# design.net
KiCad netlist of a schematic drawn in Altium Designer
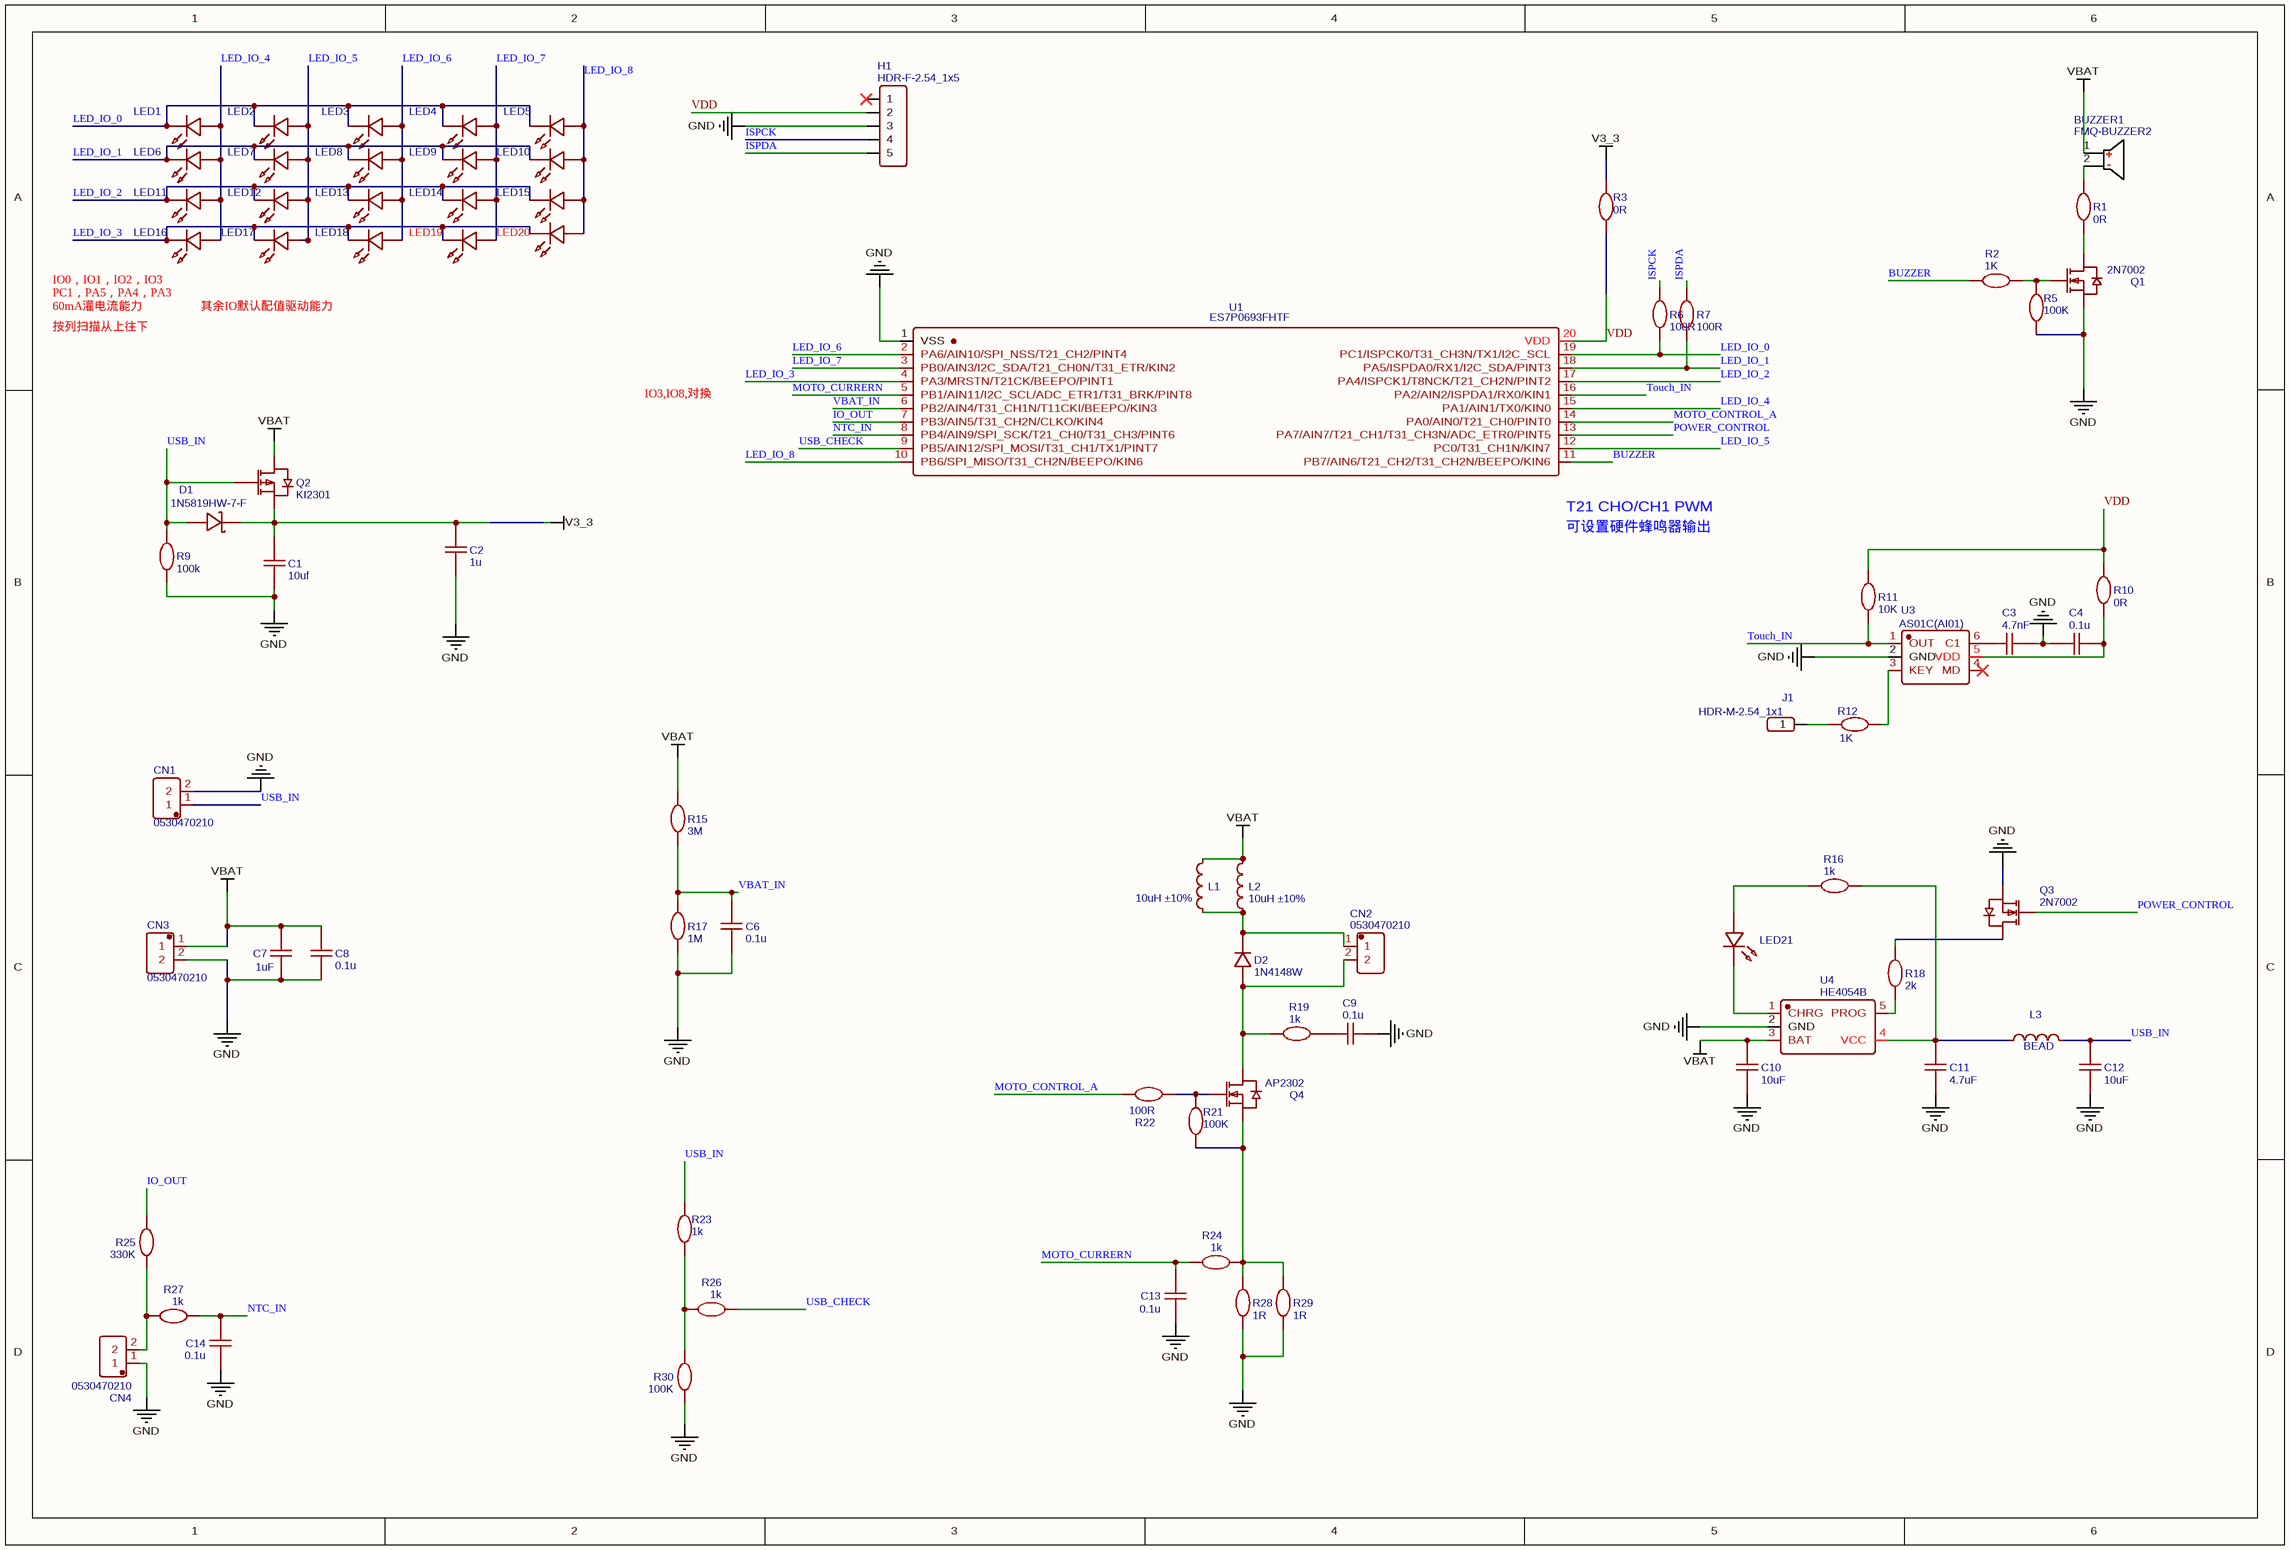
[diagram p0: 搅拌杯原理图.schdoc]

(export (version "E")
  (design (tool "Eeschema 10.0.6"))
  (components
    (comp (ref "BUZZER1")
      (value "FMQ-BUZZER2")
      (footprint "BUZ-TH_BD12.0-P7.60-D0.6-FD")
      (fields (field (name "BOM_SUPPLIER PART") "C9900006103") (field (name "CONTRIBUTOR") "LCSC"))
      (libsource (lib "altium-import") (part "root_0_FMQ-BUZZER2_"))
    )
    (comp (ref "C1")
      (value "10uf")
      (footprint "C0603")
      (fields
        (field (name "BOM_SUPPLIER PART") "C87148")
        (field (name "BOM_MANUFACTURER PART") "JMK105CBJ106MV-F")
        (field (name "CONTRIBUTOR") "LCEDA_Lib")
      )
      (libsource (lib "altium-import") (part "root_1_10uf_"))
    )
    (comp (ref "C2")
      (value "1u")
      (footprint "C0603")
      (fields (field (name "CONTRIBUTOR") "LCEDA_Lib"))
      (libsource (lib "altium-import") (part "root_1_1u_"))
    )
    (comp (ref "C3")
      (value "4.7nF")
      (footprint "C0603")
      (fields (field (name "CONTRIBUTOR") "LCEDA_Lib"))
      (libsource (lib "altium-import") (part "root_0_4.7nF_"))
    )
    (comp (ref "C4")
      (value "0.1u")
      (footprint "C0603")
      (fields (field (name "CONTRIBUTOR") "LCEDA_Lib"))
      (libsource (lib "altium-import") (part "root_0_0.1u_"))
    )
    (comp (ref "C6")
      (value "0.1u")
      (footprint "C0603")
      (fields (field (name "CONTRIBUTOR") "LCEDA_Lib"))
      (libsource (lib "") (part "root_1_0.1u__1"))
    )
    (comp (ref "C7")
      (value "1uF")
      (footprint "C0603")
      (fields (field (name "CONTRIBUTOR") "LCEDA_Lib"))
      (libsource (lib "altium-import") (part "root_3_1uF_"))
    )
    (comp (ref "C8")
      (value "0.1u")
      (footprint "C0603")
      (fields (field (name "CONTRIBUTOR") "LCEDA_Lib"))
      (libsource (lib "") (part "root_3_0.1u__1"))
    )
    (comp (ref "C9")
      (value "0.1u")
      (footprint "C0603")
      (fields (field (name "CONTRIBUTOR") "LCEDA_Lib"))
      (libsource (lib "altium-import") (part "root_2_0.1u_"))
    )
    (comp (ref "C10")
      (value "10uF")
      (footprint "C0603")
      (fields (field (name "CONTRIBUTOR") "LCEDA_Lib"))
      (libsource (lib "altium-import") (part "root_1_10uF_"))
    )
    (comp (ref "C11")
      (value "4.7uF")
      (footprint "C0603")
      (fields (field (name "CONTRIBUTOR") "LCEDA_Lib"))
      (libsource (lib "altium-import") (part "root_1_4.7uF_"))
    )
    (comp (ref "C12")
      (value "10uF")
      (footprint "C0603")
      (fields (field (name "CONTRIBUTOR") "LCEDA_Lib"))
      (libsource (lib "altium-import") (part "root_1_10uF_"))
    )
    (comp (ref "C13")
      (value "0.1u")
      (footprint "C0603")
      (fields (field (name "CONTRIBUTOR") "LCEDA_Lib"))
      (libsource (lib "altium-import") (part "root_1_0.1u_"))
    )
    (comp (ref "C14")
      (value "0.1u")
      (footprint "C0603")
      (fields (field (name "CONTRIBUTOR") "LCEDA_Lib"))
      (libsource (lib "altium-import") (part "root_3_0.1u_"))
    )
    (comp (ref "CN1")
      (value "0530470210")
      (footprint "CONN-TH_0530470210")
      (fields (field (name "BOM_SUPPLIER PART") "C114130") (field (name "CONTRIBUTOR") "LCSC"))
      (libsource (lib "altium-import") (part "root_0_mirrored_0530470210_"))
    )
    (comp (ref "CN2")
      (value "0530470210")
      (footprint "CONN-TH_0530470210")
      (fields (field (name "BOM_SUPPLIER PART") "C114130") (field (name "CONTRIBUTOR") "LCSC"))
      (libsource (lib "altium-import") (part "root_0_0530470210_"))
    )
    (comp (ref "CN3")
      (value "0530470210")
      (footprint "CONN-TH_0530470210")
      (fields (field (name "BOM_SUPPLIER PART") "C114130") (field (name "CONTRIBUTOR") "LCSC"))
      (libsource (lib "") (part "root_0_mirrored_0530470210__1"))
    )
    (comp (ref "CN4")
      (value "0530470210")
      (footprint "CONN-TH_0530470210")
      (fields (field (name "BOM_SUPPLIER PART") "C114130") (field (name "CONTRIBUTOR") "LCSC"))
      (libsource (lib "") (part "root_0_0530470210__1"))
    )
    (comp (ref "D1")
      (value "1N5819HW-7-F")
      (footprint "SOD-123_L2.8-W1.8-LS3.7-FD")
      (fields (field (name "BOM_SUPPLIER PART") "C82544"))
      (libsource (lib "altium-import") (part "root_0_1N5819HW-7-F_"))
    )
    (comp (ref "D2")
      (value "1N4148W")
      (footprint "SOD-123FL_L2.6-W1.6-LS3.4-RD")
      (fields (field (name "BOM_SUPPLIER PART") "C129216") (field (name "CONTRIBUTOR") "LCEDA_Lib"))
      (libsource (lib "altium-import") (part "root_1_1N4148W_"))
    )
    (comp (ref "H1")
      (value "HDR-F-2.54_1x5")
      (footprint "1.27mm_5PIN")
      (fields (field (name "BOM_SUPPLIER PART") "C50950") (field (name "CONTRIBUTOR") "LCEDA_Lib"))
      (libsource (lib "altium-import") (part "root_0_HDR-F-2.54_1x5_"))
    )
    (comp (ref "J1")
      (value "HDR-M-2.54_1x1")
      (footprint "HDR-M-2.54_1X1")
      (fields (field (name "BOM_SUPPLIER PART") "C81276") (field (name "CONTRIBUTOR") "LCEDA_Lib"))
      (libsource (lib "altium-import") (part "root_2_HDR-M-2.54_1x1_"))
    )
    (comp (ref "L1")
      (value "10uH ±10%")
      (footprint "L0603")
      (fields (field (name "CONTRIBUTOR") "LCEDA_Lib"))
      (libsource (lib "altium-import") (part "root_1_22uH_"))
    )
    (comp (ref "L2")
      (value "10uH ±10%")
      (footprint "L0603")
      (fields (field (name "CONTRIBUTOR") "LCEDA_Lib"))
      (libsource (lib "altium-import") (part "root_1_22uH_"))
    )
    (comp (ref "L3")
      (value "BEAD")
      (footprint "L0603")
      (fields (field (name "CONTRIBUTOR") "LCEDA_Lib"))
      (libsource (lib "altium-import") (part "root_0_22uH_"))
    )
    (comp (ref "LED1")
      (value "LED-0603_W")
      (footprint "LED0603-FD_WHITE")
      (fields
        (field (name "BOM_MANUFACTURER PART") "17-21SURC/S530-A3/TR8")
        (field (name "BOM_SUPPLIER PART") "C72037")
        (field (name "CONTRIBUTOR") "LCEDA_Lib")
      )
      (libsource (lib "altium-import") (part "root_2_LED-0603_W_"))
    )
    (comp (ref "LED2")
      (value "LED-0603_W")
      (footprint "LED0603-FD_WHITE")
      (fields
        (field (name "BOM_MANUFACTURER PART") "17-21SURC/S530-A3/TR8")
        (field (name "BOM_SUPPLIER PART") "C72037")
        (field (name "CONTRIBUTOR") "LCEDA_Lib")
      )
      (libsource (lib "altium-import") (part "root_2_LED-0603_W_"))
    )
    (comp (ref "LED3")
      (value "LED-0603_W")
      (footprint "LED0603-FD_WHITE")
      (fields
        (field (name "BOM_MANUFACTURER PART") "17-21SURC/S530-A3/TR8")
        (field (name "BOM_SUPPLIER PART") "C72037")
        (field (name "CONTRIBUTOR") "LCEDA_Lib")
      )
      (libsource (lib "altium-import") (part "root_2_LED-0603_W_"))
    )
    (comp (ref "LED4")
      (value "LED-0603_W")
      (footprint "LED0603-FD_WHITE")
      (fields
        (field (name "BOM_MANUFACTURER PART") "17-21SURC/S530-A3/TR8")
        (field (name "BOM_SUPPLIER PART") "C72037")
        (field (name "CONTRIBUTOR") "LCEDA_Lib")
      )
      (libsource (lib "altium-import") (part "root_2_LED-0603_W_"))
    )
    (comp (ref "LED5")
      (value "LED-0603_W")
      (footprint "LED0603-FD_WHITE")
      (fields
        (field (name "BOM_MANUFACTURER PART") "17-21SURC/S530-A3/TR8")
        (field (name "BOM_SUPPLIER PART") "C72037")
        (field (name "CONTRIBUTOR") "LCEDA_Lib")
      )
      (libsource (lib "altium-import") (part "root_2_LED-0603_W_"))
    )
    (comp (ref "LED6")
      (value "LED-0603_W")
      (footprint "LED0603-FD_WHITE")
      (fields
        (field (name "BOM_MANUFACTURER PART") "17-21SURC/S530-A3/TR8")
        (field (name "BOM_SUPPLIER PART") "C72037")
        (field (name "CONTRIBUTOR") "LCEDA_Lib")
      )
      (libsource (lib "altium-import") (part "root_2_LED-0603_W_"))
    )
    (comp (ref "LED7")
      (value "LED-0603_W")
      (footprint "LED0603-FD_WHITE")
      (fields
        (field (name "BOM_MANUFACTURER PART") "17-21SURC/S530-A3/TR8")
        (field (name "BOM_SUPPLIER PART") "C72037")
        (field (name "CONTRIBUTOR") "LCEDA_Lib")
      )
      (libsource (lib "altium-import") (part "root_2_LED-0603_W_"))
    )
    (comp (ref "LED8")
      (value "LED-0603_W")
      (footprint "LED0603-FD_WHITE")
      (fields
        (field (name "BOM_MANUFACTURER PART") "17-21SURC/S530-A3/TR8")
        (field (name "BOM_SUPPLIER PART") "C72037")
        (field (name "CONTRIBUTOR") "LCEDA_Lib")
      )
      (libsource (lib "altium-import") (part "root_2_LED-0603_W_"))
    )
    (comp (ref "LED9")
      (value "LED-0603_W")
      (footprint "LED0603-FD_WHITE")
      (fields
        (field (name "BOM_MANUFACTURER PART") "17-21SURC/S530-A3/TR8")
        (field (name "BOM_SUPPLIER PART") "C72037")
        (field (name "CONTRIBUTOR") "LCEDA_Lib")
      )
      (libsource (lib "altium-import") (part "root_2_LED-0603_W_"))
    )
    (comp (ref "LED10")
      (value "LED-0603_W")
      (footprint "LED0603-FD_WHITE")
      (fields
        (field (name "BOM_MANUFACTURER PART") "17-21SURC/S530-A3/TR8")
        (field (name "BOM_SUPPLIER PART") "C72037")
        (field (name "CONTRIBUTOR") "LCEDA_Lib")
      )
      (libsource (lib "altium-import") (part "root_2_LED-0603_W_"))
    )
    (comp (ref "LED11")
      (value "LED-0603_W")
      (footprint "LED0603-FD_WHITE")
      (fields
        (field (name "BOM_MANUFACTURER PART") "17-21SURC/S530-A3/TR8")
        (field (name "BOM_SUPPLIER PART") "C72037")
        (field (name "CONTRIBUTOR") "LCEDA_Lib")
      )
      (libsource (lib "altium-import") (part "root_2_LED-0603_W_"))
    )
    (comp (ref "LED12")
      (value "LED-0603_W")
      (footprint "LED0603-FD_WHITE")
      (fields
        (field (name "BOM_MANUFACTURER PART") "17-21SURC/S530-A3/TR8")
        (field (name "BOM_SUPPLIER PART") "C72037")
        (field (name "CONTRIBUTOR") "LCEDA_Lib")
      )
      (libsource (lib "altium-import") (part "root_2_LED-0603_W_"))
    )
    (comp (ref "LED13")
      (value "LED-0603_W")
      (footprint "LED0603-FD_WHITE")
      (fields
        (field (name "BOM_MANUFACTURER PART") "17-21SURC/S530-A3/TR8")
        (field (name "BOM_SUPPLIER PART") "C72037")
        (field (name "CONTRIBUTOR") "LCEDA_Lib")
      )
      (libsource (lib "altium-import") (part "root_2_LED-0603_W_"))
    )
    (comp (ref "LED14")
      (value "LED-0603_W")
      (footprint "LED0603-FD_WHITE")
      (fields
        (field (name "BOM_MANUFACTURER PART") "17-21SURC/S530-A3/TR8")
        (field (name "BOM_SUPPLIER PART") "C72037")
        (field (name "CONTRIBUTOR") "LCEDA_Lib")
      )
      (libsource (lib "altium-import") (part "root_2_LED-0603_W_"))
    )
    (comp (ref "LED15")
      (value "LED-0603_W")
      (footprint "LED0603-FD_WHITE")
      (fields
        (field (name "BOM_MANUFACTURER PART") "17-21SURC/S530-A3/TR8")
        (field (name "BOM_SUPPLIER PART") "C72037")
        (field (name "CONTRIBUTOR") "LCEDA_Lib")
      )
      (libsource (lib "altium-import") (part "root_2_LED-0603_W_"))
    )
    (comp (ref "LED16")
      (value "LED-0603_W")
      (footprint "LED0603-FD_WHITE")
      (fields
        (field (name "BOM_MANUFACTURER PART") "17-21SURC/S530-A3/TR8")
        (field (name "BOM_SUPPLIER PART") "C72037")
        (field (name "CONTRIBUTOR") "LCEDA_Lib")
      )
      (libsource (lib "altium-import") (part "root_2_LED-0603_W_"))
    )
    (comp (ref "LED17")
      (value "LED-0603_W")
      (footprint "LED0603-FD_WHITE")
      (fields
        (field (name "BOM_MANUFACTURER PART") "17-21SURC/S530-A3/TR8")
        (field (name "BOM_SUPPLIER PART") "C72037")
        (field (name "CONTRIBUTOR") "LCEDA_Lib")
      )
      (libsource (lib "altium-import") (part "root_2_LED-0603_W_"))
    )
    (comp (ref "LED18")
      (value "LED-0603_W")
      (footprint "LED0603-FD_WHITE")
      (fields
        (field (name "BOM_MANUFACTURER PART") "17-21SURC/S530-A3/TR8")
        (field (name "BOM_SUPPLIER PART") "C72037")
        (field (name "CONTRIBUTOR") "LCEDA_Lib")
      )
      (libsource (lib "altium-import") (part "root_2_LED-0603_W_"))
    )
    (comp (ref "LED19")
      (value "LED-0603_W")
      (footprint "LED0603-FD_WHITE")
      (fields
        (field (name "BOM_MANUFACTURER PART") "17-21SURC/S530-A3/TR8")
        (field (name "BOM_SUPPLIER PART") "C72037")
        (field (name "CONTRIBUTOR") "LCEDA_Lib")
      )
      (libsource (lib "altium-import") (part "root_2_LED-0603_W_"))
    )
    (comp (ref "LED20")
      (value "LED-0603_W")
      (footprint "LED0603-FD_WHITE")
      (fields
        (field (name "BOM_MANUFACTURER PART") "17-21SURC/S530-A3/TR8")
        (field (name "BOM_SUPPLIER PART") "C72037")
        (field (name "CONTRIBUTOR") "LCEDA_Lib")
      )
      (libsource (lib "altium-import") (part "root_2_LED-0603_W_"))
    )
    (comp (ref "LED21")
      (value "LED-0603_W")
      (footprint "LED0603-FD_WHITE")
      (fields
        (field (name "BOM_MANUFACTURER PART") "17-21SURC/S530-A3/TR8")
        (field (name "BOM_SUPPLIER PART") "C72037")
        (field (name "CONTRIBUTOR") "LCEDA_Lib")
      )
      (libsource (lib "altium-import") (part "root_3_LED-0603_W_"))
    )
    (comp (ref "Q1")
      (value "2N7002")
      (footprint "SOT-23_L2.9-W1.3-P0.95-LS2.4-BR")
      (fields
        (field (name "BOM_MANUFACTURER PART") "2N7002,215")
        (field (name "BOM_SUPPLIER PART") "C65189")
        (field (name "CONTRIBUTOR") "LCEDA_Lib")
      )
      (libsource (lib "") (part "root_2_2N7002__1"))
    )
    (comp (ref "Q2")
      (value "KI2301")
      (footprint "SOT-23-3_L2.9-W1.3-P1.90-LS2.4-BR")
      (fields (field (name "BOM_SUPPLIER PART") "C688914") (field (name "CONTRIBUTOR") "LCSC"))
      (libsource (lib "altium-import") (part "root_0_KI2301_"))
    )
    (comp (ref "Q3")
      (value "2N7002")
      (footprint "SOT-23_L2.9-W1.3-P0.95-LS2.4-BR")
      (fields
        (field (name "BOM_MANUFACTURER PART") "2N7002,215")
        (field (name "BOM_SUPPLIER PART") "C65189")
        (field (name "CONTRIBUTOR") "LCEDA_Lib")
      )
      (libsource (lib "altium-import") (part "root_2_2N7002_"))
    )
    (comp (ref "Q4")
      (value "AP2302")
      (footprint "SOT-23_L2.9-W1.3-P0.95-LS2.4-BR")
      (fields
        (field (name "BOM_MANUFACTURER PART") "2N7002,215")
        (field (name "BOM_SUPPLIER PART") "C65189")
        (field (name "CONTRIBUTOR") "LCEDA_Lib")
      )
      (libsource (lib "") (part "root_2_2N7002__1"))
    )
    (comp (ref "R1")
      (value "0R")
      (footprint "R0603")
      (fields (field (name "CONTRIBUTOR") "LCEDA_Lib"))
      (libsource (lib "altium-import") (part "root_3_100R_"))
    )
    (comp (ref "R2")
      (value "1K")
      (footprint "R0603")
      (fields (field (name "CONTRIBUTOR") "LCEDA_Lib"))
      (libsource (lib "altium-import") (part "root_2_1K_"))
    )
    (comp (ref "R3")
      (value "0R")
      (footprint "R1206")
      (fields (field (name "CONTRIBUTOR") "LCEDA_Lib"))
      (libsource (lib "altium-import") (part "root_1_1R_"))
    )
    (comp (ref "R5")
      (value "100K")
      (footprint "R0603")
      (fields (field (name "CONTRIBUTOR") "LCEDA_Lib"))
      (libsource (lib "altium-import") (part "root_3_1K_"))
    )
    (comp (ref "R6")
      (value "100R")
      (footprint "R0603")
      (fields (field (name "CONTRIBUTOR") "LCEDA_Lib"))
      (libsource (lib "altium-import") (part "root_3_100R_"))
    )
    (comp (ref "R7")
      (value "100R")
      (footprint "R0603")
      (fields (field (name "CONTRIBUTOR") "LCEDA_Lib"))
      (libsource (lib "altium-import") (part "root_3_100R_"))
    )
    (comp (ref "R9")
      (value "100k")
      (footprint "C0603")
      (fields (field (name "CONTRIBUTOR") "LCEDA_Lib"))
      (libsource (lib "altium-import") (part "root_1_100k_"))
    )
    (comp (ref "R10")
      (value "0R")
      (footprint "R0603")
      (fields (field (name "CONTRIBUTOR") "LCEDA_Lib"))
      (libsource (lib "altium-import") (part "root_1_NC_"))
    )
    (comp (ref "R11")
      (value "10K")
      (footprint "R0603")
      (fields (field (name "CONTRIBUTOR") "LCEDA_Lib"))
      (libsource (lib "altium-import") (part "root_1_NC_"))
    )
    (comp (ref "R12")
      (value "1K")
      (footprint "R0603")
      (fields (field (name "CONTRIBUTOR") "LCEDA_Lib"))
      (libsource (lib "altium-import") (part "root_2_1K_"))
    )
    (comp (ref "R15")
      (value "3M")
      (footprint "R0603")
      (fields (field (name "CONTRIBUTOR") "LCEDA_Lib"))
      (libsource (lib "altium-import") (part "root_1_430k_"))
    )
    (comp (ref "R16")
      (value "1k")
      (footprint "R0603")
      (fields (field (name "CONTRIBUTOR") "LCEDA_Lib"))
      (libsource (lib "") (part "root_2_1k__1"))
    )
    (comp (ref "R17")
      (value "1M")
      (footprint "R0603")
      (fields (field (name "CONTRIBUTOR") "LCEDA_Lib"))
      (libsource (lib "altium-import") (part "root_1_430K_"))
    )
    (comp (ref "R18")
      (value "2k")
      (footprint "R0603")
      (fields (field (name "CONTRIBUTOR") "LCEDA_Lib"))
      (libsource (lib "altium-import") (part "root_1_1k_"))
    )
    (comp (ref "R19")
      (value "1k")
      (footprint "R0603")
      (fields (field (name "CONTRIBUTOR") "LCEDA_Lib"))
      (libsource (lib "") (part "root_2_1k__1"))
    )
    (comp (ref "R21")
      (value "100K")
      (footprint "R0603")
      (fields (field (name "CONTRIBUTOR") "LCEDA_Lib"))
      (libsource (lib "altium-import") (part "root_3_1K_"))
    )
    (comp (ref "R22")
      (value "100R")
      (footprint "R0603")
      (fields (field (name "CONTRIBUTOR") "LCEDA_Lib"))
      (libsource (lib "altium-import") (part "root_2_100R_"))
    )
    (comp (ref "R23")
      (value "1k")
      (footprint "R0603")
      (fields (field (name "CONTRIBUTOR") "LCEDA_Lib"))
      (libsource (lib "altium-import") (part "root_3_1k_"))
    )
    (comp (ref "R24")
      (value "1k")
      (footprint "R0603")
      (fields (field (name "CONTRIBUTOR") "LCEDA_Lib"))
      (libsource (lib "altium-import") (part "root_0_1k_"))
    )
    (comp (ref "R25")
      (value "330K")
      (footprint "R0603")
      (fields (field (name "CONTRIBUTOR") "LCEDA_Lib"))
      (libsource (lib "altium-import") (part "root_3_33K_"))
    )
    (comp (ref "R26")
      (value "1k")
      (footprint "R0603")
      (fields (field (name "CONTRIBUTOR") "LCEDA_Lib"))
      (libsource (lib "altium-import") (part "root_2_1k_"))
    )
    (comp (ref "R27")
      (value "1k")
      (footprint "R0603")
      (fields (field (name "CONTRIBUTOR") "LCEDA_Lib"))
      (libsource (lib "altium-import") (part "root_2_1k_"))
    )
    (comp (ref "R28")
      (value "1R")
      (footprint "R1206")
      (fields (field (name "CONTRIBUTOR") "LCEDA_Lib"))
      (libsource (lib "altium-import") (part "root_1_1R_"))
    )
    (comp (ref "R29")
      (value "1R")
      (footprint "R1206")
      (fields (field (name "CONTRIBUTOR") "LCEDA_Lib"))
      (libsource (lib "altium-import") (part "root_1_1R_"))
    )
    (comp (ref "R30")
      (value "100K")
      (footprint "R0603")
      (fields (field (name "CONTRIBUTOR") "LCEDA_Lib"))
      (libsource (lib "altium-import") (part "root_3_33K_"))
    )
    (comp (ref "U1")
      (value "ES7P0693FHTF")
      (footprint "TSOP20")
      (fields (field (name "CONTRIBUTOR") "zime_zl"))
      (libsource (lib "altium-import") (part "root_0_ES7P0693FHTF_"))
    )
    (comp (ref "U3")
      (value "AS01C(AI01)")
      (footprint "SOT-23-6_L2.9-W1.6-P0.95-LS2.8-BL")
      (fields (field (name "BOM_SUPPLIER PART") "C389617") (field (name "CONTRIBUTOR") "LCSC"))
      (libsource (lib "altium-import") (part "root_0_AS01C(AI01)_"))
    )
    (comp (ref "U4")
      (value "HE4054B")
      (footprint "SOT-23-5_L3.0-W1.7-P0.95-LS2.8-BR")
      (fields (field (name "BOM_SUPPLIER PART") "C711953") (field (name "CONTRIBUTOR") "LCSC"))
      (libsource (lib "altium-import") (part "root_0_HE4054B_"))
    )
  )
  (nets
    (net (code "1") (name "/BUZZER") (class "Default")
      (node (ref "R2") (pin "2") (pinfunction "2_2") (pintype "passive"))
      (node (ref "U1") (pin "11") (pinfunction "PB7/AIN6/T21_CH2/T31_CH2N/BEEPO/KIN6_11") (pintype "passive"))
    )
    (net (code "2") (name "/IO_OUT") (class "Default")
      (node (ref "R25") (pin "1") (pinfunction "1_1") (pintype "passive"))
      (node (ref "U1") (pin "7") (pinfunction "PB3/AIN5/T31_CH2N/CLKO/KIN4_7") (pintype "passive"))
    )
    (net (code "3") (name "/ISPCK") (class "Default")
      (node (ref "H1") (pin "4") (pinfunction "4_4") (pintype "passive"))
      (node (ref "R6") (pin "1") (pinfunction "1_1") (pintype "passive"))
    )
    (net (code "4") (name "/ISPDA") (class "Default")
      (node (ref "H1") (pin "5") (pinfunction "5_5") (pintype "passive"))
      (node (ref "R7") (pin "1") (pinfunction "1_1") (pintype "passive"))
    )
    (net (code "5") (name "/LED_IO_0") (class "Default")
      (node (ref "LED1") (pin "2") (pinfunction "2_2") (pintype "passive"))
      (node (ref "LED2") (pin "2") (pinfunction "2_2") (pintype "passive"))
      (node (ref "LED3") (pin "2") (pinfunction "2_2") (pintype "passive"))
      (node (ref "LED4") (pin "2") (pinfunction "2_2") (pintype "passive"))
      (node (ref "LED5") (pin "2") (pinfunction "2_2") (pintype "passive"))
      (node (ref "R6") (pin "2") (pinfunction "2_2") (pintype "passive"))
      (node (ref "U1") (pin "19") (pinfunction "PC1/ISPCK0/T31_CH3N/TX1/I2C_SCL_19") (pintype "passive"))
    )
    (net (code "6") (name "/LED_IO_1") (class "Default")
      (node (ref "LED10") (pin "2") (pinfunction "2_2") (pintype "passive"))
      (node (ref "LED6") (pin "2") (pinfunction "2_2") (pintype "passive"))
      (node (ref "LED7") (pin "2") (pinfunction "2_2") (pintype "passive"))
      (node (ref "LED8") (pin "2") (pinfunction "2_2") (pintype "passive"))
      (node (ref "LED9") (pin "2") (pinfunction "2_2") (pintype "passive"))
      (node (ref "R7") (pin "2") (pinfunction "2_2") (pintype "passive"))
      (node (ref "U1") (pin "18") (pinfunction "PA5/ISPDA0/RX1/I2C_SDA/PINT3_18") (pintype "passive"))
    )
    (net (code "7") (name "/LED_IO_2") (class "Default")
      (node (ref "LED11") (pin "2") (pinfunction "2_2") (pintype "passive"))
      (node (ref "LED12") (pin "2") (pinfunction "2_2") (pintype "passive"))
      (node (ref "LED13") (pin "2") (pinfunction "2_2") (pintype "passive"))
      (node (ref "LED14") (pin "2") (pinfunction "2_2") (pintype "passive"))
      (node (ref "LED15") (pin "2") (pinfunction "2_2") (pintype "passive"))
      (node (ref "U1") (pin "17") (pinfunction "PA4/ISPCK1/T8NCK/T21_CH2N/PINT2_17") (pintype "passive"))
    )
    (net (code "8") (name "/LED_IO_3") (class "Default")
      (node (ref "LED16") (pin "2") (pinfunction "2_2") (pintype "passive"))
      (node (ref "LED17") (pin "2") (pinfunction "2_2") (pintype "passive"))
      (node (ref "LED18") (pin "2") (pinfunction "2_2") (pintype "passive"))
      (node (ref "LED19") (pin "2") (pinfunction "2_2") (pintype "passive"))
      (node (ref "LED20") (pin "2") (pinfunction "2_2") (pintype "passive"))
      (node (ref "U1") (pin "4") (pinfunction "PA3/MRSTN/T21CK/BEEPO/PINT1_4") (pintype "passive"))
    )
    (net (code "9") (name "/LED_IO_4") (class "Default")
      (node (ref "LED1") (pin "1") (pinfunction "1_1") (pintype "passive"))
      (node (ref "LED11") (pin "1") (pinfunction "1_1") (pintype "passive"))
      (node (ref "LED16") (pin "1") (pinfunction "1_1") (pintype "passive"))
      (node (ref "LED6") (pin "1") (pinfunction "1_1") (pintype "passive"))
      (node (ref "U1") (pin "15") (pinfunction "PA1/AIN1/TX0/KIN0_15") (pintype "passive"))
    )
    (net (code "10") (name "/LED_IO_5") (class "Default")
      (node (ref "LED12") (pin "1") (pinfunction "1_1") (pintype "passive"))
      (node (ref "LED17") (pin "1") (pinfunction "1_1") (pintype "passive"))
      (node (ref "LED2") (pin "1") (pinfunction "1_1") (pintype "passive"))
      (node (ref "LED7") (pin "1") (pinfunction "1_1") (pintype "passive"))
      (node (ref "U1") (pin "12") (pinfunction "PC0/T31_CH1N/KIN7_12") (pintype "passive"))
    )
    (net (code "11") (name "/LED_IO_6") (class "Default")
      (node (ref "LED13") (pin "1") (pinfunction "1_1") (pintype "passive"))
      (node (ref "LED18") (pin "1") (pinfunction "1_1") (pintype "passive"))
      (node (ref "LED3") (pin "1") (pinfunction "1_1") (pintype "passive"))
      (node (ref "LED8") (pin "1") (pinfunction "1_1") (pintype "passive"))
      (node (ref "U1") (pin "2") (pinfunction "PA6/AIN10/SPI_NSS/T21_CH2/PINT4_2") (pintype "passive"))
    )
    (net (code "12") (name "/LED_IO_7") (class "Default")
      (node (ref "LED14") (pin "1") (pinfunction "1_1") (pintype "passive"))
      (node (ref "LED19") (pin "1") (pinfunction "1_1") (pintype "passive"))
      (node (ref "LED4") (pin "1") (pinfunction "1_1") (pintype "passive"))
      (node (ref "LED9") (pin "1") (pinfunction "1_1") (pintype "passive"))
      (node (ref "U1") (pin "3") (pinfunction "PB0/AIN3/I2C_SDA/T21_CH0N/T31_ETR/KIN2_3") (pintype "passive"))
    )
    (net (code "13") (name "/LED_IO_8") (class "Default")
      (node (ref "LED10") (pin "1") (pinfunction "1_1") (pintype "passive"))
      (node (ref "LED15") (pin "1") (pinfunction "1_1") (pintype "passive"))
      (node (ref "LED20") (pin "1") (pinfunction "1_1") (pintype "passive"))
      (node (ref "LED5") (pin "1") (pinfunction "1_1") (pintype "passive"))
      (node (ref "U1") (pin "10") (pinfunction "PB6/SPI_MISO/T31_CH2N/BEEPO/KIN6_10") (pintype "passive"))
    )
    (net (code "14") (name "/MOTO_CONTROL_A") (class "Default")
      (node (ref "R22") (pin "1") (pinfunction "1_1") (pintype "passive"))
      (node (ref "U1") (pin "14") (pinfunction "PA0/AIN0/T21_CH0/PINT0_14") (pintype "passive"))
    )
    (net (code "15") (name "/MOTO_CURRERN") (class "Default")
      (node (ref "C13") (pin "2") (pinfunction "2_2") (pintype "passive"))
      (node (ref "R24") (pin "2") (pinfunction "2_2") (pintype "passive"))
      (node (ref "U1") (pin "5") (pinfunction "PB1/AIN11/I2C_SCL/ADC_ETR1/T31_BRK/PINT8_5") (pintype "passive"))
    )
    (net (code "16") (name "/NTC_IN") (class "Default")
      (node (ref "C14") (pin "1") (pinfunction "1_1") (pintype "passive"))
      (node (ref "R27") (pin "2") (pinfunction "2_2") (pintype "passive"))
      (node (ref "U1") (pin "8") (pinfunction "PB4/AIN9/SPI_SCK/T21_CH0/T31_CH3/PINT6_8") (pintype "passive"))
    )
    (net (code "17") (name "/POWER_CONTROL") (class "Default")
      (node (ref "Q3") (pin "1") (pinfunction "G_1") (pintype "passive"))
      (node (ref "U1") (pin "13") (pinfunction "PA7/AIN7/T21_CH1/T31_CH3N/ADC_ETR0/PINT5_13") (pintype "passive"))
    )
    (net (code "18") (name "/Touch_IN") (class "Default")
      (node (ref "R11") (pin "1") (pinfunction "1_1") (pintype "passive"))
      (node (ref "U1") (pin "16") (pinfunction "PA2/AIN2/ISPDA1/RX0/KIN1_16") (pintype "passive"))
      (node (ref "U3") (pin "1") (pinfunction "OUT_1") (pintype "passive"))
    )
    (net (code "19") (name "/USB_CHECK") (class "Default")
      (node (ref "R26") (pin "2") (pinfunction "2_2") (pintype "passive"))
      (node (ref "U1") (pin "9") (pinfunction "PB5/AIN12/SPI_MOSI/T31_CH1/TX1/PINT7_9") (pintype "passive"))
    )
    (net (code "20") (name "/USB_IN") (class "Default")
      (node (ref "C12") (pin "2") (pinfunction "2_2") (pintype "passive"))
      (node (ref "CN1") (pin "1") (pinfunction "1_1") (pintype "passive"))
      (node (ref "D1") (pin "1") (pinfunction "A_1") (pintype "passive"))
      (node (ref "L3") (pin "2") (pinfunction "2_2") (pintype "passive"))
      (node (ref "Q2") (pin "1") (pinfunction "G_1") (pintype "passive"))
      (node (ref "R23") (pin "2") (pinfunction "2_2") (pintype "passive"))
      (node (ref "R9") (pin "2") (pinfunction "2_2") (pintype "passive"))
    )
    (net (code "21") (name "/VBAT_IN") (class "Default")
      (node (ref "C6") (pin "2") (pinfunction "2_2") (pintype "passive"))
      (node (ref "R15") (pin "1") (pinfunction "1_1") (pintype "passive"))
      (node (ref "R17") (pin "2") (pinfunction "2_2") (pintype "passive"))
      (node (ref "U1") (pin "6") (pinfunction "PB2/AIN4/T31_CH1N/T11CKI/BEEPO/KIN3_6") (pintype "passive"))
    )
    (net (code "22") (name "/VDD") (class "Default")
      (node (ref "H1") (pin "2") (pinfunction "2_2") (pintype "passive"))
      (node (ref "R10") (pin "2") (pinfunction "2_2") (pintype "passive"))
      (node (ref "R11") (pin "2") (pinfunction "2_2") (pintype "passive"))
      (node (ref "R3") (pin "1") (pinfunction "1_1") (pintype "passive"))
      (node (ref "U1") (pin "20") (pinfunction "VDD_20") (pintype "passive"))
    )
    (net (code "23") (name "GND") (class "Default")
      (node (ref "C1") (pin "1") (pinfunction "1_1") (pintype "passive"))
      (node (ref "C10") (pin "1") (pinfunction "1_1") (pintype "passive"))
      (node (ref "C11") (pin "1") (pinfunction "1_1") (pintype "passive"))
      (node (ref "C12") (pin "1") (pinfunction "1_1") (pintype "passive"))
      (node (ref "C13") (pin "1") (pinfunction "1_1") (pintype "passive"))
      (node (ref "C14") (pin "2") (pinfunction "2_2") (pintype "passive"))
      (node (ref "C2") (pin "1") (pinfunction "1_1") (pintype "passive"))
      (node (ref "C3") (pin "2") (pinfunction "2_2") (pintype "passive"))
      (node (ref "C4") (pin "1") (pinfunction "1_1") (pintype "passive"))
      (node (ref "C6") (pin "1") (pinfunction "1_1") (pintype "passive"))
      (node (ref "C7") (pin "2") (pinfunction "2_2") (pintype "passive"))
      (node (ref "C8") (pin "2") (pinfunction "2_2") (pintype "passive"))
      (node (ref "C9") (pin "1") (pinfunction "1_1") (pintype "passive"))
      (node (ref "CN1") (pin "2") (pinfunction "2_2") (pintype "passive"))
      (node (ref "CN3") (pin "2") (pinfunction "2_2") (pintype "passive"))
      (node (ref "CN4") (pin "1") (pinfunction "1_1") (pintype "passive"))
      (node (ref "H1") (pin "3") (pinfunction "3_3") (pintype "passive"))
      (node (ref "Q1") (pin "2") (pinfunction "S_2") (pintype "passive"))
      (node (ref "Q3") (pin "2") (pinfunction "S_2") (pintype "passive"))
      (node (ref "R17") (pin "1") (pinfunction "1_1") (pintype "passive"))
      (node (ref "R28") (pin "1") (pinfunction "1_1") (pintype "passive"))
      (node (ref "R29") (pin "1") (pinfunction "1_1") (pintype "passive"))
      (node (ref "R30") (pin "2") (pinfunction "2_2") (pintype "passive"))
      (node (ref "R5") (pin "2") (pinfunction "2_2") (pintype "passive"))
      (node (ref "R9") (pin "1") (pinfunction "1_1") (pintype "passive"))
      (node (ref "U1") (pin "1") (pinfunction "VSS_1") (pintype "passive"))
      (node (ref "U3") (pin "2") (pinfunction "GND_2") (pintype "passive"))
      (node (ref "U4") (pin "2") (pinfunction "GND_2") (pintype "passive"))
    )
    (net (code "24") (name "Net-(BUZZER1-Pad2)") (class "Default")
      (node (ref "BUZZER1") (pin "2") (pinfunction "2_2") (pintype "passive"))
      (node (ref "R1") (pin "1") (pinfunction "1_1") (pintype "passive"))
    )
    (net (code "25") (name "Net-(C9-Pad2)") (class "Default")
      (node (ref "C9") (pin "2") (pinfunction "2_2") (pintype "passive"))
      (node (ref "R19") (pin "1") (pinfunction "1_1") (pintype "passive"))
    )
    (net (code "26") (name "Net-(CN2-Pad1)") (class "Default")
      (node (ref "CN2") (pin "1") (pinfunction "1_1") (pintype "passive"))
      (node (ref "D2") (pin "1") (pinfunction "1_1") (pintype "passive"))
      (node (ref "L1") (pin "1") (pinfunction "1_1") (pintype "passive"))
      (node (ref "L2") (pin "1") (pinfunction "1_1") (pintype "passive"))
    )
    (net (code "27") (name "Net-(CN4-Pad2)") (class "Default")
      (node (ref "CN4") (pin "2") (pinfunction "2_2") (pintype "passive"))
      (node (ref "R25") (pin "2") (pinfunction "2_2") (pintype "passive"))
      (node (ref "R27") (pin "1") (pinfunction "1_1") (pintype "passive"))
    )
    (net (code "28") (name "Net-(J1-Pad1)") (class "Default")
      (node (ref "J1") (pin "1") (pinfunction "1_1") (pintype "passive"))
      (node (ref "R12") (pin "2") (pinfunction "2_2") (pintype "passive"))
    )
    (net (code "29") (name "Net-(LED21-Pad1)") (class "Default")
      (node (ref "LED21") (pin "1") (pinfunction "1_1") (pintype "passive"))
      (node (ref "R16") (pin "2") (pinfunction "2_2") (pintype "passive"))
    )
    (net (code "30") (name "Net-(Q1-D)") (class "Default")
      (node (ref "Q1") (pin "3") (pinfunction "D_3") (pintype "passive"))
      (node (ref "R1") (pin "2") (pinfunction "2_2") (pintype "passive"))
    )
    (net (code "31") (name "Net-(Q1-G)") (class "Default")
      (node (ref "Q1") (pin "1") (pinfunction "G_1") (pintype "passive"))
      (node (ref "R2") (pin "1") (pinfunction "1_1") (pintype "passive"))
      (node (ref "R5") (pin "1") (pinfunction "1_1") (pintype "passive"))
    )
    (net (code "32") (name "Net-(Q3-D)") (class "Default")
      (node (ref "Q3") (pin "3") (pinfunction "D_3") (pintype "passive"))
      (node (ref "R18") (pin "2") (pinfunction "2_2") (pintype "passive"))
    )
    (net (code "33") (name "Net-(Q4-D)") (class "Default")
      (node (ref "CN2") (pin "2") (pinfunction "2_2") (pintype "passive"))
      (node (ref "D2") (pin "2") (pinfunction "2_2") (pintype "passive"))
      (node (ref "Q4") (pin "3") (pinfunction "D_3") (pintype "passive"))
      (node (ref "R19") (pin "2") (pinfunction "2_2") (pintype "passive"))
    )
    (net (code "34") (name "Net-(Q4-G)") (class "Default")
      (node (ref "Q4") (pin "1") (pinfunction "G_1") (pintype "passive"))
      (node (ref "R21") (pin "1") (pinfunction "1_1") (pintype "passive"))
      (node (ref "R22") (pin "2") (pinfunction "2_2") (pintype "passive"))
    )
    (net (code "35") (name "Net-(Q4-S)") (class "Default")
      (node (ref "Q4") (pin "2") (pinfunction "S_2") (pintype "passive"))
      (node (ref "R21") (pin "2") (pinfunction "2_2") (pintype "passive"))
      (node (ref "R24") (pin "1") (pinfunction "1_1") (pintype "passive"))
      (node (ref "R28") (pin "2") (pinfunction "2_2") (pintype "passive"))
      (node (ref "R29") (pin "2") (pinfunction "2_2") (pintype "passive"))
    )
    (net (code "36") (name "Net-(R23-Pad1)") (class "Default")
      (node (ref "R23") (pin "1") (pinfunction "1_1") (pintype "passive"))
      (node (ref "R26") (pin "1") (pinfunction "1_1") (pintype "passive"))
      (node (ref "R30") (pin "1") (pinfunction "1_1") (pintype "passive"))
    )
    (net (code "37") (name "Net-(U3-C1)") (class "Default")
      (node (ref "C3") (pin "1") (pinfunction "1_1") (pintype "passive"))
      (node (ref "U3") (pin "6") (pinfunction "C1_6") (pintype "passive"))
    )
    (net (code "38") (name "Net-(U3-KEY)") (class "Default")
      (node (ref "R12") (pin "1") (pinfunction "1_1") (pintype "passive"))
      (node (ref "U3") (pin "3") (pinfunction "KEY_3") (pintype "passive"))
    )
    (net (code "39") (name "Net-(U3-VDD)") (class "Default")
      (node (ref "C4") (pin "2") (pinfunction "2_2") (pintype "passive"))
      (node (ref "R10") (pin "1") (pinfunction "1_1") (pintype "passive"))
      (node (ref "U3") (pin "5") (pinfunction "VDD_5") (pintype "passive"))
    )
    (net (code "40") (name "Net-(U4-CHRG)") (class "Default")
      (node (ref "LED21") (pin "2") (pinfunction "2_2") (pintype "passive"))
      (node (ref "U4") (pin "1") (pinfunction "CHRG_1") (pintype "passive"))
    )
    (net (code "41") (name "Net-(U4-PROG)") (class "Default")
      (node (ref "R18") (pin "1") (pinfunction "1_1") (pintype "passive"))
      (node (ref "U4") (pin "5") (pinfunction "PROG_5") (pintype "passive"))
    )
    (net (code "42") (name "Net-(U4-VCC)") (class "Default")
      (node (ref "C11") (pin "2") (pinfunction "2_2") (pintype "passive"))
      (node (ref "L3") (pin "1") (pinfunction "1_1") (pintype "passive"))
      (node (ref "R16") (pin "1") (pinfunction "1_1") (pintype "passive"))
      (node (ref "U4") (pin "4") (pinfunction "VCC_4") (pintype "passive"))
    )
    (net (code "43") (name "V3_3") (class "Default")
      (node (ref "C1") (pin "2") (pinfunction "2_2") (pintype "passive"))
      (node (ref "C2") (pin "2") (pinfunction "2_2") (pintype "passive"))
      (node (ref "D1") (pin "2") (pinfunction "K_2") (pintype "passive"))
      (node (ref "Q2") (pin "2") (pinfunction "S_2") (pintype "passive"))
      (node (ref "R3") (pin "2") (pinfunction "2_2") (pintype "passive"))
    )
    (net (code "44") (name "VBAT") (class "Default")
      (node (ref "BUZZER1") (pin "1") (pinfunction "1_1") (pintype "passive"))
      (node (ref "C10") (pin "2") (pinfunction "2_2") (pintype "passive"))
      (node (ref "C7") (pin "1") (pinfunction "1_1") (pintype "passive"))
      (node (ref "C8") (pin "1") (pinfunction "1_1") (pintype "passive"))
      (node (ref "CN3") (pin "1") (pinfunction "1_1") (pintype "passive"))
      (node (ref "L1") (pin "2") (pinfunction "2_2") (pintype "passive"))
      (node (ref "L2") (pin "2") (pinfunction "2_2") (pintype "passive"))
      (node (ref "Q2") (pin "3") (pinfunction "D_3") (pintype "passive"))
      (node (ref "R15") (pin "2") (pinfunction "2_2") (pintype "passive"))
      (node (ref "U4") (pin "3") (pinfunction "BAT_3") (pintype "passive"))
    )
    (net (code "45") (name "unconnected-(H1-Pad1)") (class "Default")
      (node (ref "H1") (pin "1") (pinfunction "1_1") (pintype "passive+no_connect"))
    )
    (net (code "46") (name "unconnected-(U3-MD-Pad4)") (class "Default")
      (node (ref "U3") (pin "4") (pinfunction "MD_4") (pintype "passive+no_connect"))
    )
  )
)
